# 13_CPU_1.net
KiCad netlist of a schematic drawn in Altium Designer
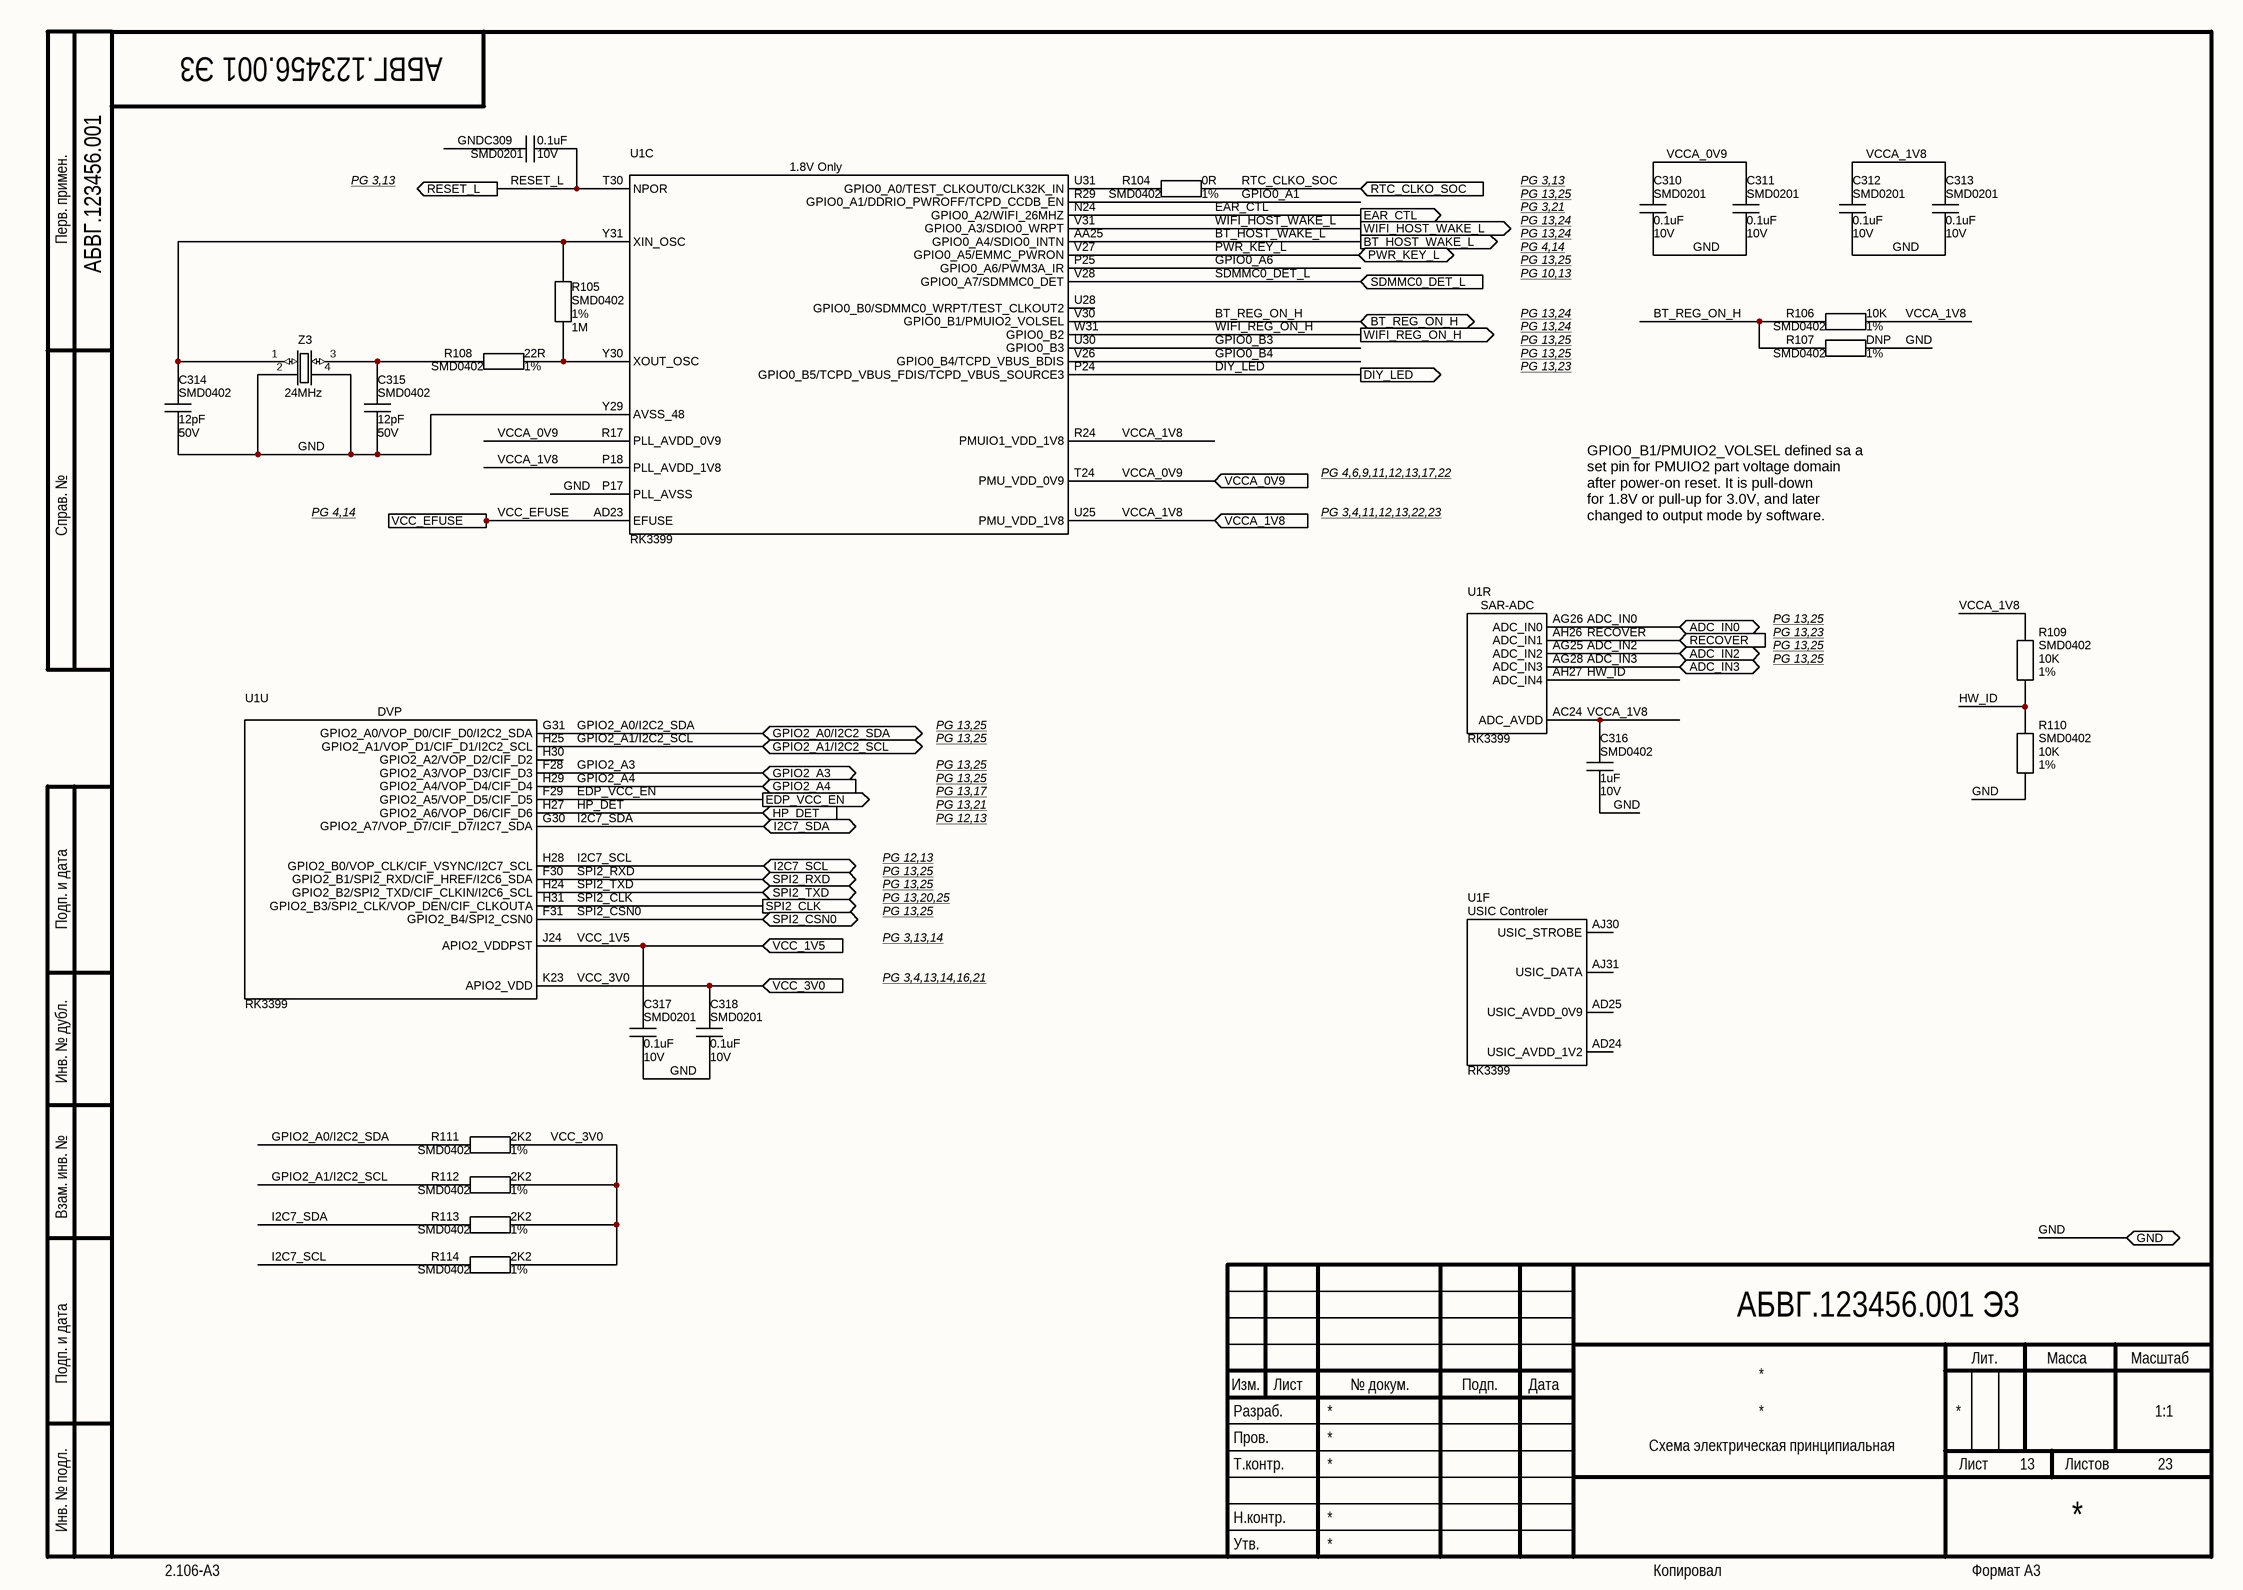
[diagram p0: 13 CPU_1.SchDoc]

(export (version "E")
  (design (tool "Eeschema 10.0.6"))
  (components
    (comp (ref "C309")
      (value "0.1uF")
      (footprint "Didur_PcbLib_1:CAP_SMD_0201")
      (fields
        (field (name "PACKAGE") "SMD0201")
        (field (name "PARTNUMBER") "CC0201KRX5R6BB104")
        (field (name "VOLTAGE") "10V")
      )
      (libsource (lib "Didur_SchLib_1") (part "Ceramic_Cap"))
    )
    (comp (ref "C310")
      (value "0.1uF")
      (footprint "Didur_PcbLib_1:CAP_SMD_0201")
      (fields
        (field (name "PACKAGE") "SMD0201")
        (field (name "PARTNUMBER") "CC0201KRX5R6BB104")
        (field (name "VOLTAGE") "10V")
      )
      (libsource (lib "Didur_SchLib_1") (part "Ceramic_Cap"))
    )
    (comp (ref "C311")
      (value "0.1uF")
      (footprint "Didur_PcbLib_1:CAP_SMD_0201")
      (fields
        (field (name "PACKAGE") "SMD0201")
        (field (name "PARTNUMBER") "CC0201KRX5R6BB104")
        (field (name "VOLTAGE") "10V")
      )
      (libsource (lib "Didur_SchLib_1") (part "Ceramic_Cap"))
    )
    (comp (ref "C312")
      (value "0.1uF")
      (footprint "Didur_PcbLib_1:CAP_SMD_0201")
      (fields
        (field (name "PACKAGE") "SMD0201")
        (field (name "PARTNUMBER") "CC0201KRX5R6BB104")
        (field (name "VOLTAGE") "10V")
      )
      (libsource (lib "Didur_SchLib_1") (part "Ceramic_Cap"))
    )
    (comp (ref "C313")
      (value "0.1uF")
      (footprint "Didur_PcbLib_1:CAP_SMD_0201")
      (fields
        (field (name "PACKAGE") "SMD0201")
        (field (name "PARTNUMBER") "CC0201KRX5R6BB104")
        (field (name "VOLTAGE") "10V")
      )
      (libsource (lib "Didur_SchLib_1") (part "Ceramic_Cap"))
    )
    (comp (ref "C314")
      (value "12pF")
      (footprint "Didur_PcbLib_1:CAP_SMD_0402")
      (fields
        (field (name "PACKAGE") "SMD0402")
        (field (name "PARTNUMBER") "CC0402JRNPO9BN120")
        (field (name "VOLTAGE") "50V")
      )
      (libsource (lib "Didur_SchLib_1") (part "Ceramic_Cap"))
    )
    (comp (ref "C315")
      (value "12pF")
      (footprint "Didur_PcbLib_1:CAP_SMD_0402")
      (fields
        (field (name "PACKAGE") "SMD0402")
        (field (name "PARTNUMBER") "CC0402JRNPO9BN120")
        (field (name "VOLTAGE") "50V")
      )
      (libsource (lib "Didur_SchLib_1") (part "Ceramic_Cap"))
    )
    (comp (ref "C316")
      (value "1uF")
      (footprint "Didur_PcbLib_1:CAP_SMD_0402_small")
      (fields
        (field (name "PACKAGE") "SMD0402")
        (field (name "PARTNUMBER") "CC0402KRX5R6BB105")
        (field (name "VOLTAGE") "10V")
      )
      (libsource (lib "Didur_SchLib_1") (part "Ceramic_Cap"))
    )
    (comp (ref "C317")
      (value "0.1uF")
      (footprint "Didur_PcbLib_1:CAP_SMD_0201")
      (fields
        (field (name "PACKAGE") "SMD0201")
        (field (name "PARTNUMBER") "CC0201KRX5R6BB104")
        (field (name "VOLTAGE") "10V")
      )
      (libsource (lib "Didur_SchLib_1") (part "Ceramic_Cap"))
    )
    (comp (ref "C318")
      (value "0.1uF")
      (footprint "Didur_PcbLib_1:CAP_SMD_0201")
      (fields
        (field (name "PACKAGE") "SMD0201")
        (field (name "PARTNUMBER") "CC0201KRX5R6BB104")
        (field (name "VOLTAGE") "10V")
      )
      (libsource (lib "Didur_SchLib_1") (part "Ceramic_Cap"))
    )
    (comp (ref "R104")
      (value "0R")
      (footprint "Didur_PcbLib_1:RES_SMD_0402")
      (fields
        (field (name "PACKAGE") "SMD0402")
        (field (name "PARTNUMBER") "RC0402FR-070RL")
        (field (name "TOLERANCE") "1%")
      )
      (libsource (lib "") (part "Chip_Res_3"))
    )
    (comp (ref "R105")
      (value "1M")
      (footprint "Didur_PcbLib_1:RES_SMD_0402")
      (fields
        (field (name "PACKAGE") "SMD0402")
        (field (name "PARTNUMBER") "RC0402FR-071ML")
        (field (name "TOLERANCE") "1%")
      )
      (libsource (lib "") (part "Chip_Res_3"))
    )
    (comp (ref "R106")
      (value "10K")
      (footprint "Didur_PcbLib_1:RES_SMD_0402")
      (fields
        (field (name "PACKAGE") "SMD0402")
        (field (name "PARTNUMBER") "RC0402FR-0710KL")
        (field (name "TOLERANCE") "1%")
      )
      (libsource (lib "") (part "Chip_Res_1"))
    )
    (comp (ref "R107")
      (value "DNP")
      (footprint "Didur_PcbLib_1:RES_SMD_0402")
      (fields
        (field (name "PACKAGE") "SMD0402")
        (field (name "PARTNUMBER") "Do Not Place")
        (field (name "TOLERANCE") "1%")
      )
      (libsource (lib "") (part "Chip_Res_3"))
    )
    (comp (ref "R108")
      (value "22R")
      (footprint "Didur_PcbLib_1:RES_SMD_0402")
      (fields
        (field (name "PACKAGE") "SMD0402")
        (field (name "PARTNUMBER") "RC0402FR-0722RL")
        (field (name "TOLERANCE") "1%")
      )
      (libsource (lib "Didur_SchLib_1") (part "Chip_Res"))
    )
    (comp (ref "R109")
      (value "10K")
      (footprint "Didur_PcbLib_1:RES_SMD_0402")
      (fields
        (field (name "PACKAGE") "SMD0402")
        (field (name "PARTNUMBER") "RC0402FR-0710KL")
        (field (name "TOLERANCE") "1%")
      )
      (libsource (lib "") (part "Chip_Res_2"))
    )
    (comp (ref "R110")
      (value "10K")
      (footprint "Didur_PcbLib_1:RES_SMD_0402")
      (fields
        (field (name "PACKAGE") "SMD0402")
        (field (name "PARTNUMBER") "RC0402FR-0710KL")
        (field (name "TOLERANCE") "1%")
      )
      (libsource (lib "") (part "Chip_Res_2"))
    )
    (comp (ref "R111")
      (value "2K2")
      (footprint "Didur_PcbLib_1:RES_SMD_0402")
      (fields
        (field (name "PACKAGE") "SMD0402")
        (field (name "PARTNUMBER") "RC0402FR-072K2L")
        (field (name "TOLERANCE") "1%")
      )
      (libsource (lib "Didur_SchLib_1") (part "Chip_Res"))
    )
    (comp (ref "R112")
      (value "2K2")
      (footprint "Didur_PcbLib_1:RES_SMD_0402")
      (fields
        (field (name "PACKAGE") "SMD0402")
        (field (name "PARTNUMBER") "RC0402FR-072K2L")
        (field (name "TOLERANCE") "1%")
      )
      (libsource (lib "Didur_SchLib_1") (part "Chip_Res"))
    )
    (comp (ref "R113")
      (value "2K2")
      (footprint "Didur_PcbLib_1:RES_SMD_0402")
      (fields
        (field (name "PACKAGE") "SMD0402")
        (field (name "PARTNUMBER") "RC0402FR-072K2L")
        (field (name "TOLERANCE") "1%")
      )
      (libsource (lib "Didur_SchLib_1") (part "Chip_Res"))
    )
    (comp (ref "R114")
      (value "2K2")
      (footprint "Didur_PcbLib_1:RES_SMD_0402")
      (fields
        (field (name "PACKAGE") "SMD0402")
        (field (name "PARTNUMBER") "RC0402FR-072K2L")
        (field (name "TOLERANCE") "1%")
      )
      (libsource (lib "Didur_SchLib_1") (part "Chip_Res"))
    )
    (comp (ref "U1")
      (value "RK3399")
      (footprint "BGA828C65P31X31_2100X2100X161N")
      (fields (field (name "Comment") "RK3399_FF"))
      (libsource (lib "Didur_SchLib_1") (part "RK3399_FF"))
    )
    (comp (ref "Z3")
      (value "24MHz")
      (footprint "Didur_PcbLib_1:TSX3225")
      (fields (field (name "PARTNUMBER") "12.88665") (field (name "Comment") "Value"))
      (libsource (lib "Didur_SchLib_1") (part "OSC3225"))
    )
  )
  (nets
    (net (code "1") (name "/ADC_IN0") (class "Default")
      (node (ref "U1") (pin "AG26") (pinfunction "ADC_IN0_AG26") (pintype "passive"))
    )
    (net (code "2") (name "/ADC_IN2") (class "Default")
      (node (ref "U1") (pin "AG25") (pinfunction "ADC_IN2_AG25") (pintype "passive"))
    )
    (net (code "3") (name "/ADC_IN3") (class "Default")
      (node (ref "U1") (pin "AG28") (pinfunction "ADC_IN3_AG28") (pintype "passive"))
    )
    (net (code "4") (name "/BT_HOST_WAKE_L") (class "Default")
      (node (ref "U1") (pin "AA25") (pinfunction "GPIO0_A4/SDIO0_INTN_AA25") (pintype "passive"))
    )
    (net (code "5") (name "/BT_REG_ON_H") (class "Default")
      (node (ref "R106") (pin "2") (pinfunction "2_2") (pintype "passive"))
      (node (ref "R107") (pin "1") (pinfunction "1_1") (pintype "passive"))
      (node (ref "U1") (pin "V30") (pinfunction "GPIO0_B1/PMUIO2_VOLSEL_V30") (pintype "passive"))
    )
    (net (code "6") (name "/DIY_LED") (class "Default")
      (node (ref "U1") (pin "P24") (pinfunction "GPIO0_B5/TCPD_VBUS_FDIS/TCPD_VBUS_SOURCE3_P24") (pintype "passive"))
    )
    (net (code "7") (name "/EAR_CTL") (class "Default")
      (node (ref "U1") (pin "N24") (pinfunction "GPIO0_A2/WIFI_26MHZ_N24") (pintype "passive"))
    )
    (net (code "8") (name "/EDP_VCC_EN") (class "Default")
      (node (ref "U1") (pin "F29") (pinfunction "GPIO2_A5/VOP_D5/CIF_D5_F29") (pintype "passive"))
    )
    (net (code "9") (name "/GND") (class "Default")
      (node (ref "C309") (pin "1") (pinfunction "1_1") (pintype "power_in"))
      (node (ref "C310") (pin "2") (pinfunction "2_2") (pintype "power_in"))
      (node (ref "C311") (pin "2") (pinfunction "2_2") (pintype "power_in"))
      (node (ref "C312") (pin "2") (pinfunction "2_2") (pintype "power_in"))
      (node (ref "C313") (pin "2") (pinfunction "2_2") (pintype "power_in"))
      (node (ref "C314") (pin "2") (pinfunction "2_2") (pintype "power_in"))
      (node (ref "C315") (pin "2") (pinfunction "2_2") (pintype "power_in"))
      (node (ref "C316") (pin "2") (pinfunction "2_2") (pintype "power_in"))
      (node (ref "C317") (pin "2") (pinfunction "2_2") (pintype "power_in"))
      (node (ref "C318") (pin "2") (pinfunction "2_2") (pintype "power_in"))
      (node (ref "R107") (pin "2") (pinfunction "2_2") (pintype "passive"))
      (node (ref "R110") (pin "1") (pinfunction "1_1") (pintype "passive"))
      (node (ref "U1") (pin "P17") (pinfunction "PLL_AVSS_P17") (pintype "passive"))
      (node (ref "U1") (pin "Y29") (pinfunction "AVSS_48_Y29") (pintype "passive"))
      (node (ref "Z3") (pin "2") (pinfunction "GND_2") (pintype "passive"))
      (node (ref "Z3") (pin "4") (pinfunction "GND_4") (pintype "passive"))
    )
    (net (code "10") (name "/GPIO0_A1") (class "Default")
      (node (ref "U1") (pin "R29") (pinfunction "GPIO0_A1/DDRIO_PWROFF/TCPD_CCDB_EN_R29") (pintype "passive"))
    )
    (net (code "11") (name "/GPIO0_A6") (class "Default")
      (node (ref "U1") (pin "P25") (pinfunction "GPIO0_A6/PWM3A_IR_P25") (pintype "passive"))
    )
    (net (code "12") (name "/GPIO0_B3") (class "Default")
      (node (ref "U1") (pin "U30") (pinfunction "GPIO0_B3_U30") (pintype "passive"))
    )
    (net (code "13") (name "/GPIO0_B4") (class "Default")
      (node (ref "U1") (pin "V26") (pinfunction "GPIO0_B4/TCPD_VBUS_BDIS_V26") (pintype "passive"))
    )
    (net (code "14") (name "/GPIO2_A0{slash}I2C2_SDA") (class "Default")
      (node (ref "R111") (pin "2") (pinfunction "2_2") (pintype "passive"))
      (node (ref "U1") (pin "G31") (pinfunction "GPIO2_A0/VOP_D0/CIF_D0/I2C2_SDA_G31") (pintype "passive"))
    )
    (net (code "15") (name "/GPIO2_A1{slash}I2C2_SCL") (class "Default")
      (node (ref "R112") (pin "2") (pinfunction "2_2") (pintype "passive"))
      (node (ref "U1") (pin "H25") (pinfunction "GPIO2_A1/VOP_D1/CIF_D1/I2C2_SCL_H25") (pintype "passive"))
    )
    (net (code "16") (name "/GPIO2_A3") (class "Default")
      (node (ref "U1") (pin "F28") (pinfunction "GPIO2_A3/VOP_D3/CIF_D3_F28") (pintype "passive"))
    )
    (net (code "17") (name "/GPIO2_A4") (class "Default")
      (node (ref "U1") (pin "H29") (pinfunction "GPIO2_A4/VOP_D4/CIF_D4_H29") (pintype "passive"))
    )
    (net (code "18") (name "/HP_DET") (class "Default")
      (node (ref "U1") (pin "H27") (pinfunction "GPIO2_A6/VOP_D6/CIF_D6_H27") (pintype "passive"))
    )
    (net (code "19") (name "/HW_ID") (class "Default")
      (node (ref "R109") (pin "1") (pinfunction "1_1") (pintype "passive"))
      (node (ref "R110") (pin "2") (pinfunction "2_2") (pintype "passive"))
      (node (ref "U1") (pin "AH27") (pinfunction "ADC_IN4_AH27") (pintype "passive"))
    )
    (net (code "20") (name "/I2C7_SCL") (class "Default")
      (node (ref "R114") (pin "2") (pinfunction "2_2") (pintype "passive"))
      (node (ref "U1") (pin "H28") (pinfunction "GPIO2_B0/VOP_CLK/CIF_VSYNC/I2C7_SCL_H28") (pintype "passive"))
    )
    (net (code "21") (name "/I2C7_SDA") (class "Default")
      (node (ref "R113") (pin "2") (pinfunction "2_2") (pintype "passive"))
      (node (ref "U1") (pin "G30") (pinfunction "GPIO2_A7/VOP_D7/CIF_D7/I2C7_SDA_G30") (pintype "passive"))
    )
    (net (code "22") (name "/PWR_KEY_L") (class "Default")
      (node (ref "U1") (pin "V27") (pinfunction "GPIO0_A5/EMMC_PWRON_V27") (pintype "passive"))
    )
    (net (code "23") (name "/RECOVER") (class "Default")
      (node (ref "U1") (pin "AH26") (pinfunction "ADC_IN1_AH26") (pintype "passive"))
    )
    (net (code "24") (name "/RESET_L") (class "Default")
      (node (ref "C309") (pin "2") (pinfunction "2_2") (pintype "power_in"))
      (node (ref "U1") (pin "T30") (pinfunction "NPOR_T30") (pintype "passive"))
    )
    (net (code "25") (name "/RTC_CLKO_SOC") (class "Default")
      (node (ref "R104") (pin "2") (pinfunction "2_2") (pintype "passive"))
    )
    (net (code "26") (name "/SDMMC0_DET_L") (class "Default")
      (node (ref "U1") (pin "V28") (pinfunction "GPIO0_A7/SDMMC0_DET_V28") (pintype "passive"))
    )
    (net (code "27") (name "/SPI2_CLK") (class "Default")
      (node (ref "U1") (pin "H31") (pinfunction "GPIO2_B3/SPI2_CLK/VOP_DEN/CIF_CLKOUTA_H31") (pintype "passive"))
    )
    (net (code "28") (name "/SPI2_CSN0") (class "Default")
      (node (ref "U1") (pin "F31") (pinfunction "GPIO2_B4/SPI2_CSN0_F31") (pintype "passive"))
    )
    (net (code "29") (name "/SPI2_RXD") (class "Default")
      (node (ref "U1") (pin "F30") (pinfunction "GPIO2_B1/SPI2_RXD/CIF_HREF/I2C6_SDA_F30") (pintype "passive"))
    )
    (net (code "30") (name "/SPI2_TXD") (class "Default")
      (node (ref "U1") (pin "H24") (pinfunction "GPIO2_B2/SPI2_TXD/CIF_CLKIN/I2C6_SCL_H24") (pintype "passive"))
    )
    (net (code "31") (name "/VCCA_0V9") (class "Default")
      (node (ref "C310") (pin "1") (pinfunction "1_1") (pintype "power_in"))
      (node (ref "C311") (pin "1") (pinfunction "1_1") (pintype "power_in"))
      (node (ref "U1") (pin "R17") (pinfunction "PLL_AVDD_0V9_R17") (pintype "passive"))
      (node (ref "U1") (pin "T24") (pinfunction "PMU_VDD_0V9_T24") (pintype "passive"))
    )
    (net (code "32") (name "/VCCA_1V8") (class "Default")
      (node (ref "C312") (pin "1") (pinfunction "1_1") (pintype "power_in"))
      (node (ref "C313") (pin "1") (pinfunction "1_1") (pintype "power_in"))
      (node (ref "C316") (pin "1") (pinfunction "1_1") (pintype "power_in"))
      (node (ref "R106") (pin "1") (pinfunction "1_1") (pintype "passive"))
      (node (ref "R109") (pin "2") (pinfunction "2_2") (pintype "passive"))
      (node (ref "U1") (pin "AC24") (pinfunction "ADC_AVDD_AC24") (pintype "passive"))
      (node (ref "U1") (pin "P18") (pinfunction "PLL_AVDD_1V8_P18") (pintype "passive"))
      (node (ref "U1") (pin "R24") (pinfunction "PMUIO1_VDD_1V8_R24") (pintype "passive"))
      (node (ref "U1") (pin "U25") (pinfunction "PMU_VDD_1V8_U25") (pintype "passive"))
    )
    (net (code "33") (name "/VCC_1V5") (class "Default")
      (node (ref "C317") (pin "1") (pinfunction "1_1") (pintype "power_in"))
      (node (ref "U1") (pin "J24") (pinfunction "APIO2_VDDPST_J24") (pintype "passive"))
    )
    (net (code "34") (name "/VCC_3V0") (class "Default")
      (node (ref "C318") (pin "1") (pinfunction "1_1") (pintype "power_in"))
      (node (ref "R111") (pin "1") (pinfunction "1_1") (pintype "passive"))
      (node (ref "R112") (pin "1") (pinfunction "1_1") (pintype "passive"))
      (node (ref "R113") (pin "1") (pinfunction "1_1") (pintype "passive"))
      (node (ref "R114") (pin "1") (pinfunction "1_1") (pintype "passive"))
      (node (ref "U1") (pin "K23") (pinfunction "APIO2_VDD_K23") (pintype "passive"))
    )
    (net (code "35") (name "/VCC_EFUSE") (class "Default")
      (node (ref "U1") (pin "AD23") (pinfunction "EFUSE_AD23") (pintype "passive"))
    )
    (net (code "36") (name "/WIFI_HOST_WAKE_L") (class "Default")
      (node (ref "U1") (pin "V31") (pinfunction "GPIO0_A3/SDIO0_WRPT_V31") (pintype "passive"))
    )
    (net (code "37") (name "/WIFI_REG_ON_H") (class "Default")
      (node (ref "U1") (pin "W31") (pinfunction "GPIO0_B2_W31") (pintype "passive"))
    )
    (net (code "38") (name "Net-(C315-Pad1)") (class "Default")
      (node (ref "C315") (pin "1") (pinfunction "1_1") (pintype "power_in"))
      (node (ref "R108") (pin "2") (pinfunction "2_2") (pintype "passive"))
      (node (ref "Z3") (pin "3") (pinfunction "IN/OUT_3") (pintype "bidirectional"))
    )
    (net (code "39") (name "Net-(U1C-GPIO0_A0{slash}TEST_CLKOUT0{slash}CLK32K_IN)") (class "Default")
      (node (ref "R104") (pin "1") (pinfunction "1_1") (pintype "passive"))
      (node (ref "U1") (pin "U31") (pinfunction "GPIO0_A0/TEST_CLKOUT0/CLK32K_IN_U31") (pintype "passive"))
    )
    (net (code "40") (name "Net-(U1C-XIN_OSC)") (class "Default")
      (node (ref "C314") (pin "1") (pinfunction "1_1") (pintype "power_in"))
      (node (ref "R105") (pin "2") (pinfunction "2_2") (pintype "passive"))
      (node (ref "U1") (pin "Y31") (pinfunction "XIN_OSC_Y31") (pintype "passive"))
      (node (ref "Z3") (pin "1") (pinfunction "IN/OUT_1") (pintype "bidirectional"))
    )
    (net (code "41") (name "Net-(U1C-XOUT_OSC)") (class "Default")
      (node (ref "R105") (pin "1") (pinfunction "1_1") (pintype "passive"))
      (node (ref "R108") (pin "1") (pinfunction "1_1") (pintype "passive"))
      (node (ref "U1") (pin "Y30") (pinfunction "XOUT_OSC_Y30") (pintype "passive"))
    )
    (net (code "42") (name "unconnected-(U1C-GPIO0_B0{slash}SDMMC0_WRPT{slash}TEST_CLKOUT2-PadU28)") (class "Default")
      (node (ref "U1") (pin "U28") (pinfunction "GPIO0_B0/SDMMC0_WRPT/TEST_CLKOUT2_U28") (pintype "passive"))
    )
    (net (code "43") (name "unconnected-(U1F-USIC_AVDD_0V9-PadAD25)") (class "Default")
      (node (ref "U1") (pin "AD25") (pinfunction "USIC_AVDD_0V9_AD25") (pintype "passive"))
    )
    (net (code "44") (name "unconnected-(U1F-USIC_AVDD_1V2-PadAD24)") (class "Default")
      (node (ref "U1") (pin "AD24") (pinfunction "USIC_AVDD_1V2_AD24") (pintype "passive"))
    )
    (net (code "45") (name "unconnected-(U1F-USIC_DATA-PadAJ31)") (class "Default")
      (node (ref "U1") (pin "AJ31") (pinfunction "USIC_DATA_AJ31") (pintype "passive"))
    )
    (net (code "46") (name "unconnected-(U1F-USIC_STROBE-PadAJ30)") (class "Default")
      (node (ref "U1") (pin "AJ30") (pinfunction "USIC_STROBE_AJ30") (pintype "passive"))
    )
    (net (code "47") (name "unconnected-(U1U-GPIO2_A2{slash}VOP_D2{slash}CIF_D2-PadH30)") (class "Default")
      (node (ref "U1") (pin "H30") (pinfunction "GPIO2_A2/VOP_D2/CIF_D2_H30") (pintype "passive"))
    )
  )
)
